# Power_Sheet.net
KiCad netlist of a schematic drawn in Altium Designer
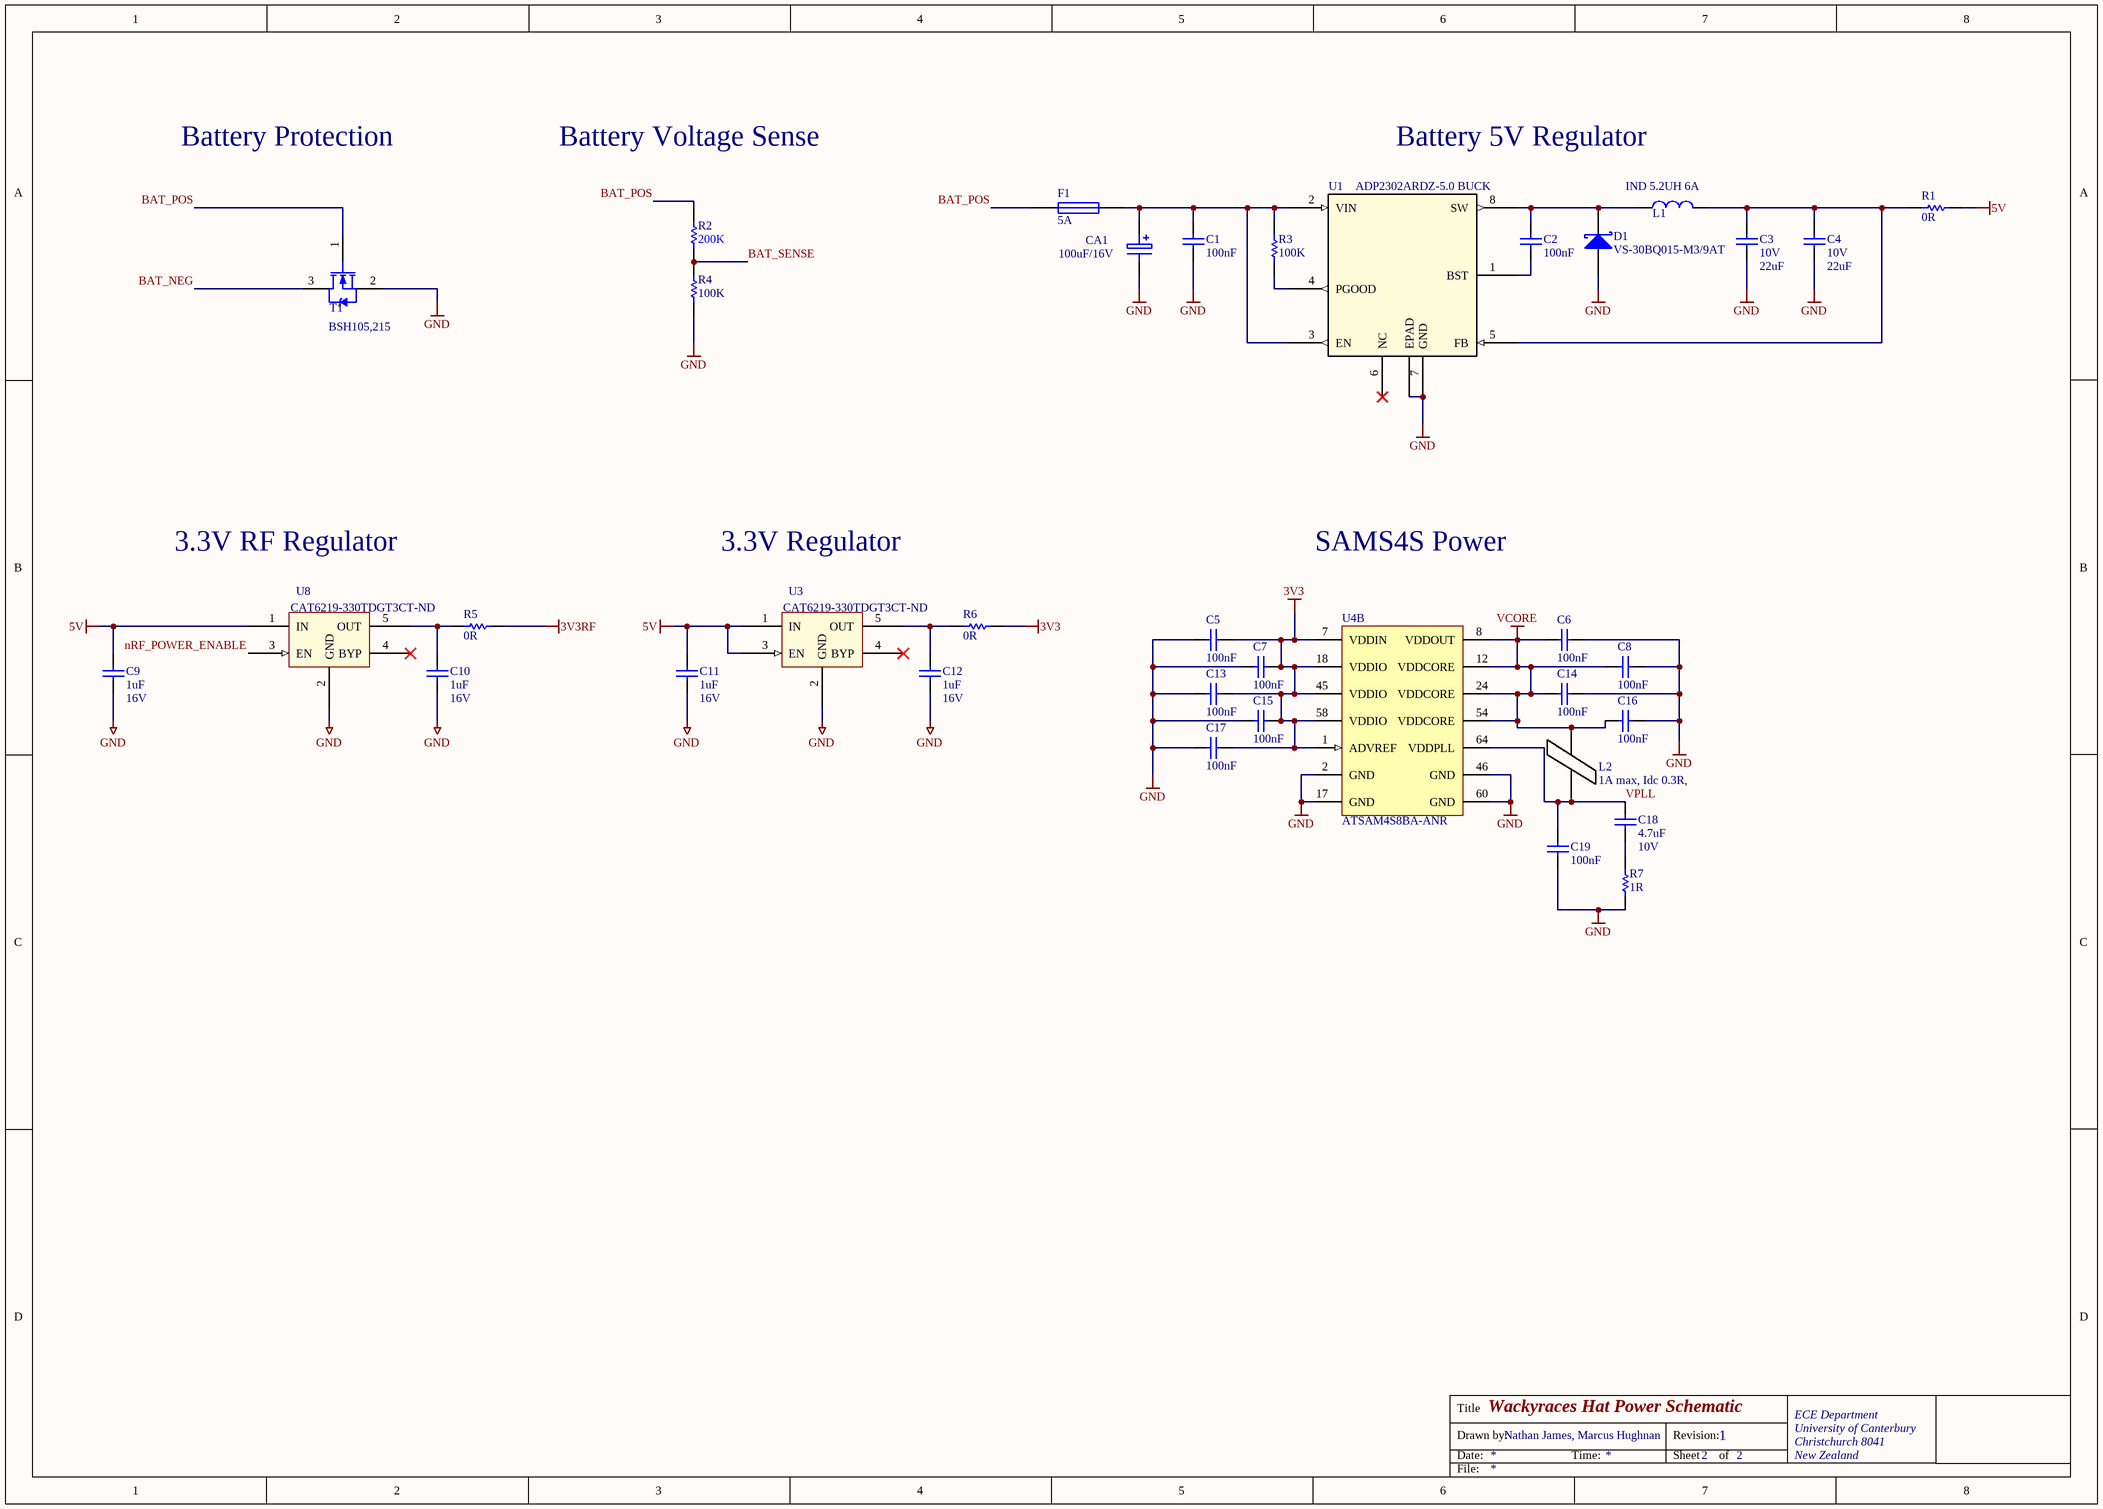
[diagram p0: Power Sheet.SchDoc]

(export (version "E")
  (design (tool "Eeschema 10.0.6"))
  (components
    (comp (ref "C1")
      (value "100nF")
      (footprint "CAPC1608L")
      (description "CAP CER 100nF X7R +-10% 50V 0603")
      (libsource (lib "ECE AD19Components_19V1") (part "CC_100nF_0603"))
    )
    (comp (ref "C2")
      (value "100nF")
      (footprint "CAPC1608L")
      (description "CAP CER 100nF X7R +-10% 50V 0603")
      (libsource (lib "ECE AD19Components_19V1") (part "CC_100nF_0603"))
    )
    (comp (ref "C3")
      (value "22uF")
      (footprint "CAPC3216L")
      (description "CAP CER 22uF Y5V -20% +80% 10V 1206")
      (fields (field (name "MAX VOLTAGE") "10V"))
      (libsource (lib "ECE AD19Components_19V1") (part "CC_22uF_1206"))
    )
    (comp (ref "C4")
      (value "22uF")
      (footprint "CAPC3216L")
      (description "CAP CER 22uF Y5V -20% +80% 10V 1206")
      (fields (field (name "MAX VOLTAGE") "10V"))
      (libsource (lib "ECE AD19Components_19V1") (part "CC_22uF_1206"))
    )
    (comp (ref "C5")
      (value "100nF")
      (footprint "CAPC1608L")
      (description "CAP CER 100nF X7R +-10% 50V 0603")
      (libsource (lib "ECE AD19Components_19V1") (part "CC_100nF_0603"))
    )
    (comp (ref "C6")
      (value "100nF")
      (footprint "CAPC1608L")
      (description "CAP CER 100nF X7R +-10% 50V 0603")
      (libsource (lib "ECE AD19Components_19V1") (part "CC_100nF_0603"))
    )
    (comp (ref "C7")
      (value "100nF")
      (footprint "CAPC1608L")
      (description "CAP CER 100nF X7R +-10% 50V 0603")
      (libsource (lib "ECE AD19Components_19V1") (part "CC_100nF_0603"))
    )
    (comp (ref "C8")
      (value "100nF")
      (footprint "CAPC1608L")
      (description "CAP CER 100nF X7R +-10% 50V 0603")
      (libsource (lib "ECE AD19Components_19V1") (part "CC_100nF_0603"))
    )
    (comp (ref "C9")
      (value "1uF")
      (footprint "CAPC1608L")
      (description "CAP CER 1uF Y5V -20% +80% 16V 0603")
      (fields (field (name "MAX VOLTAGE") "16V"))
      (libsource (lib "ECE AD19Components_19V1") (part "CC_1uF_0603"))
    )
    (comp (ref "C10")
      (value "1uF")
      (footprint "CAPC1608L")
      (description "CAP CER 1uF Y5V -20% +80% 16V 0603")
      (fields (field (name "MAX VOLTAGE") "16V"))
      (libsource (lib "ECE AD19Components_19V1") (part "CC_1uF_0603"))
    )
    (comp (ref "C11")
      (value "1uF")
      (footprint "CAPC1608L")
      (description "CAP CER 1uF Y5V -20% +80% 16V 0603")
      (fields (field (name "MAX VOLTAGE") "16V"))
      (libsource (lib "ECE AD19Components_19V1") (part "CC_1uF_0603"))
    )
    (comp (ref "C12")
      (value "1uF")
      (footprint "CAPC1608L")
      (description "CAP CER 1uF Y5V -20% +80% 16V 0603")
      (fields (field (name "MAX VOLTAGE") "16V"))
      (libsource (lib "ECE AD19Components_19V1") (part "CC_1uF_0603"))
    )
    (comp (ref "C13")
      (value "100nF")
      (footprint "CAPC1608L")
      (description "CAP CER 100nF X7R +-10% 50V 0603")
      (libsource (lib "ECE AD19Components_19V1") (part "CC_100nF_0603"))
    )
    (comp (ref "C14")
      (value "100nF")
      (footprint "CAPC1608L")
      (description "CAP CER 100nF X7R +-10% 50V 0603")
      (libsource (lib "ECE AD19Components_19V1") (part "CC_100nF_0603"))
    )
    (comp (ref "C15")
      (value "100nF")
      (footprint "CAPC1608L")
      (description "CAP CER 100nF X7R +-10% 50V 0603")
      (libsource (lib "ECE AD19Components_19V1") (part "CC_100nF_0603"))
    )
    (comp (ref "C16")
      (value "100nF")
      (footprint "CAPC1608L")
      (description "CAP CER 100nF X7R +-10% 50V 0603")
      (libsource (lib "ECE AD19Components_19V1") (part "CC_100nF_0603"))
    )
    (comp (ref "C17")
      (value "100nF")
      (footprint "CAPC1608L")
      (description "CAP CER 100nF X7R +-10% 50V 0603")
      (libsource (lib "ECE AD19Components_19V1") (part "CC_100nF_0603"))
    )
    (comp (ref "C18")
      (value "4.7uF")
      (footprint "CAPC1608N")
      (description "CAP CER 4.7uF X5R +-20%  10V 0603")
      (fields (field (name "MAX VOLTAGE") "10V"))
      (libsource (lib "ECE AD19Components_19V1") (part "CC_4.7uF_0603"))
    )
    (comp (ref "C19")
      (value "100nF")
      (footprint "CAPC1608L")
      (description "CAP CER 100nF X7R +-10% 50V 0603")
      (libsource (lib "ECE AD19Components_19V1") (part "CC_100nF_0603"))
    )
    (comp (ref "CA1")
      (value "100uF/16V")
      (footprint "NICH-1")
      (description "CAP ALUM 100uF 16V SMD")
      (fields (field (name "MANUFACTURER") "Nichcon"))
      (libsource (lib "ECE AD19Components_19V1") (part "CA_100uF_16V"))
    )
    (comp (ref "D1")
      (value "VS-30BQ015-M3/9AT")
      (footprint "SMC")
      (description "DIODE, SCHOTTKY, 3A, 15V, DO-214AB / SMC")
      (fields (field (name "MANUFACTURER") "Vishay Semiconductors"))
      (libsource (lib "ECE AD19Components_19V1") (part "DS_VS-30BQ015-M3"))
    )
    (comp (ref "F1")
      (value "5A")
      (footprint "RESC3216N")
      (description "Fuse 5.0A Fast Acting 1206 SMD")
      (fields (field (name "MANUFACTURER PART NUMBER") "C1F5") (field (name "MANUFACTURER") "Bel TRP"))
      (libsource (lib "ECE AD19Components_19V1") (part "FS_Fuse_5.0A"))
    )
    (comp (ref "L1")
      (value "IND 5.2UH 6A")
      (footprint "INDUCTOR5u2")
      (description "FIXED IND 5.2UH 6A 22 MOHM SMD")
      (fields
        (field (name "MANUFACTURER") "Sumida America Components Inc.")
        (field (name "MANUFACTURER PART NUMBER") "CDRH104RNP-5R2NC")
      )
      (libsource (lib "ENCE461AD19_19V2") (part "CDRH104RNP-5R2NC"))
    )
    (comp (ref "L2")
      (value "1A max, Idc 0.3R,")
      (footprint "INDC3216L")
      (description "Ferrite Bead, Rdc 0.3R, Z100MHZ 600R, Imax 1A, SMD 1206")
      (fields
        (field (name "MANUFACTURER") "FAIR-RITE")
        (field (name "MANUFACTURER PART NUMBER") "2512066017Y1")
      )
      (libsource (lib "ECE AD19Components_19V1") (part "IN_Ferrite-Bead"))
    )
    (comp (ref "R1")
      (value "0R")
      (footprint "RESC1608L")
      (description "RES 0.0 OHM 1/10W 5% 0603 SMD")
      (libsource (lib "ECE AD19Components_19V1") (part "RS_0R0"))
    )
    (comp (ref "R2")
      (value "200K")
      (footprint "RESC1608L")
      (description "RES 200K OHM 1/10W 5% 0603 SMD")
      (libsource (lib "ECE AD19Components_19V1") (part "RS_200K"))
    )
    (comp (ref "R3")
      (value "100K")
      (footprint "RESC1608L")
      (description "RES 100K OHM 1/10W 5% 0603 SMD")
      (libsource (lib "ECE AD19Components_19V1") (part "RS_100K"))
    )
    (comp (ref "R4")
      (value "100K")
      (footprint "RESC1608L")
      (description "RES 100K OHM 1/10W 5% 0603 SMD")
      (libsource (lib "ECE AD19Components_19V1") (part "RS_100K"))
    )
    (comp (ref "R5")
      (value "0R")
      (footprint "RESC1608L")
      (description "RES 0.0 OHM 1/10W 5% 0603 SMD")
      (libsource (lib "ECE AD19Components_19V1") (part "RS_0R0"))
    )
    (comp (ref "R6")
      (value "0R")
      (footprint "RESC1608L")
      (description "RES 0.0 OHM 1/10W 5% 0603 SMD")
      (libsource (lib "ECE AD19Components_19V1") (part "RS_0R0"))
    )
    (comp (ref "R7")
      (value "1R")
      (footprint "RESC3216L")
      (description "RES 1R OHM 1/4W 5% 1206 SMD")
      (libsource (lib "ECE AD19Components_19V1") (part "RT_1R"))
    )
    (comp (ref "T1")
      (value "BSH105,215")
      (footprint "SOT23_L")
      (description "MOSFET N-CH 20V 1.05A SOT-23")
      (fields
        (field (name "MANUFACTURER") "NXP Semiconductors")
        (field (name "MANUFACTURER PART NUMBER") "BSH105,215")
      )
      (libsource (lib "ECE AD19Components_19V1") (part "TM_BSH105"))
    )
    (comp (ref "U1")
      (value "ADP2302ARDZ-5.0 BUCK")
      (footprint "RD_8_1")
      (description "IC REG BUCK 5V 2A 8SOIC")
      (fields (field (name "MANUFACTURER_PART_NUMBER") "ADP2302ARDZ-5.0-R7"))
      (libsource (lib "ENCE461AD19_19V2") (part "ADP2302ARDZ-5.0-R7"))
    )
    (comp (ref "U3")
      (value "CAT6219-330TDGT3")
      (footprint "SOT95P280X145-5N")
      (description "IC REG LIN 3.3V 500MA TSOT23-5")
      (fields
        (field (name "BASE PART NUMBER") "CAT6219")
        (field (name "SUPPLIER PART NUMBER") "CAT6219-330TDGT3CT-ND")
      )
      (libsource (lib "ENCE461AD19_19V2") (part "SV_CAT6219-330TDGT3"))
    )
    (comp (ref "U4")
      (value "ATSAM4S8BA-ANR")
      (footprint "LQFP64_L")
      (description "IC MCU 32BIT 512KB FLASH 64LQFP")
      (fields (field (name "MANUFACTURER") "Atmel"))
      (libsource (lib "ECE AD19Components_19V1") (part "SE_ATSAM4S16BA-MU"))
    )
    (comp (ref "U8")
      (value "CAT6219-330TDGT3")
      (footprint "SOT95P280X145-5N")
      (description "IC REG LIN 3.3V 500MA TSOT23-5")
      (fields
        (field (name "BASE PART NUMBER") "CAT6219")
        (field (name "SUPPLIER PART NUMBER") "CAT6219-330TDGT3CT-ND")
      )
      (libsource (lib "ENCE461AD19_19V2") (part "SV_CAT6219-330TDGT3"))
    )
  )
  (nets
    (net (code "1") (name "/BAT_NEG") (class "Default")
      (node (ref "T1") (pin "3") (pinfunction "3_3") (pintype "passive"))
    )
    (net (code "2") (name "/BAT_POS") (class "Default")
      (node (ref "F1") (pin "1") (pinfunction "1_1") (pintype "passive"))
      (node (ref "R2") (pin "2") (pinfunction "2_2") (pintype "passive"))
      (node (ref "T1") (pin "1") (pinfunction "1_1") (pintype "passive"))
    )
    (net (code "3") (name "/BAT_SENSE") (class "Default")
      (node (ref "R2") (pin "1") (pinfunction "1_1") (pintype "passive"))
      (node (ref "R4") (pin "2") (pinfunction "2_2") (pintype "passive"))
    )
    (net (code "4") (name "/VPLL") (class "Default")
      (node (ref "C18") (pin "2") (pinfunction "2_2") (pintype "passive"))
      (node (ref "C19") (pin "2") (pinfunction "2_2") (pintype "passive"))
      (node (ref "L2") (pin "1") (pinfunction "1_1") (pintype "passive"))
      (node (ref "U4") (pin "64") (pinfunction "VDDPLL_64") (pintype "power_in"))
    )
    (net (code "5") (name "/nRF_POWER_ENABLE") (class "Default")
      (node (ref "U8") (pin "3") (pinfunction "EN_3") (pintype "input"))
    )
    (net (code "6") (name "3V3") (class "Default")
      (node (ref "C13") (pin "2") (pinfunction "2_2") (pintype "passive"))
      (node (ref "C15") (pin "2") (pinfunction "2_2") (pintype "passive"))
      (node (ref "C17") (pin "2") (pinfunction "2_2") (pintype "passive"))
      (node (ref "C5") (pin "2") (pinfunction "2_2") (pintype "passive"))
      (node (ref "C7") (pin "2") (pinfunction "2_2") (pintype "passive"))
      (node (ref "R6") (pin "2") (pinfunction "2_2") (pintype "passive"))
      (node (ref "U4") (pin "1") (pinfunction "ADVREF_1") (pintype "input"))
      (node (ref "U4") (pin "18") (pinfunction "VDDIO_18") (pintype "power_in"))
      (node (ref "U4") (pin "45") (pinfunction "VDDIO_45") (pintype "power_in"))
      (node (ref "U4") (pin "58") (pinfunction "VDDIO_58") (pintype "power_in"))
      (node (ref "U4") (pin "7") (pinfunction "VDDIN_7") (pintype "power_in"))
    )
    (net (code "7") (name "3V3RF") (class "Default")
      (node (ref "R5") (pin "2") (pinfunction "2_2") (pintype "passive"))
    )
    (net (code "8") (name "5V") (class "Default")
      (node (ref "C11") (pin "2") (pinfunction "2_2") (pintype "passive"))
      (node (ref "C9") (pin "2") (pinfunction "2_2") (pintype "passive"))
      (node (ref "R1") (pin "2") (pinfunction "2_2") (pintype "passive"))
      (node (ref "U3") (pin "1") (pinfunction "IN_1") (pintype "power_in"))
      (node (ref "U3") (pin "3") (pinfunction "EN_3") (pintype "input"))
      (node (ref "U8") (pin "1") (pinfunction "IN_1") (pintype "power_in"))
    )
    (net (code "9") (name "GND") (class "Default")
      (node (ref "C1") (pin "1") (pinfunction "1_1") (pintype "passive"))
      (node (ref "C10") (pin "1") (pinfunction "1_1") (pintype "passive"))
      (node (ref "C11") (pin "1") (pinfunction "1_1") (pintype "passive"))
      (node (ref "C12") (pin "1") (pinfunction "1_1") (pintype "passive"))
      (node (ref "C13") (pin "1") (pinfunction "1_1") (pintype "passive"))
      (node (ref "C14") (pin "2") (pinfunction "2_2") (pintype "passive"))
      (node (ref "C15") (pin "1") (pinfunction "1_1") (pintype "passive"))
      (node (ref "C16") (pin "2") (pinfunction "2_2") (pintype "passive"))
      (node (ref "C17") (pin "1") (pinfunction "1_1") (pintype "passive"))
      (node (ref "C19") (pin "1") (pinfunction "1_1") (pintype "passive"))
      (node (ref "C3") (pin "1") (pinfunction "1_1") (pintype "passive"))
      (node (ref "C4") (pin "1") (pinfunction "1_1") (pintype "passive"))
      (node (ref "C5") (pin "1") (pinfunction "1_1") (pintype "passive"))
      (node (ref "C6") (pin "2") (pinfunction "2_2") (pintype "passive"))
      (node (ref "C7") (pin "1") (pinfunction "1_1") (pintype "passive"))
      (node (ref "C8") (pin "2") (pinfunction "2_2") (pintype "passive"))
      (node (ref "C9") (pin "1") (pinfunction "1_1") (pintype "passive"))
      (node (ref "CA1") (pin "1") (pintype "passive"))
      (node (ref "D1") (pin "1") (pinfunction "A_1") (pintype "passive"))
      (node (ref "R4") (pin "1") (pinfunction "1_1") (pintype "passive"))
      (node (ref "R7") (pin "1") (pinfunction "1_1") (pintype "passive"))
      (node (ref "T1") (pin "2") (pinfunction "2_2") (pintype "passive"))
      (node (ref "U1") (pin "7") (pinfunction "GND_7") (pintype "power_in"))
      (node (ref "U1") (pin "EPAD") (pinfunction "EPAD_EPAD") (pintype "passive"))
      (node (ref "U3") (pin "2") (pinfunction "GND_2") (pintype "power_in"))
      (node (ref "U4") (pin "17") (pinfunction "GND_17") (pintype "power_in"))
      (node (ref "U4") (pin "2") (pinfunction "GND_2") (pintype "power_in"))
      (node (ref "U4") (pin "46") (pinfunction "GND_46") (pintype "power_in"))
      (node (ref "U4") (pin "60") (pinfunction "GND_60") (pintype "power_in"))
      (node (ref "U8") (pin "2") (pinfunction "GND_2") (pintype "power_in"))
    )
    (net (code "10") (name "Net-(C18-Pad1)") (class "Default")
      (node (ref "C18") (pin "1") (pinfunction "1_1") (pintype "passive"))
      (node (ref "R7") (pin "2") (pinfunction "2_2") (pintype "passive"))
    )
    (net (code "11") (name "Net-(D1-K)") (class "Default")
      (node (ref "C2") (pin "2") (pinfunction "2_2") (pintype "passive"))
      (node (ref "D1") (pin "2") (pinfunction "K_2") (pintype "passive"))
      (node (ref "L1") (pin "1") (pintype "passive"))
      (node (ref "U1") (pin "8") (pinfunction "SW_8") (pintype "output"))
    )
    (net (code "12") (name "Net-(U1-BST)") (class "Default")
      (node (ref "C2") (pin "1") (pinfunction "1_1") (pintype "passive"))
      (node (ref "U1") (pin "1") (pinfunction "BST_1") (pintype "passive"))
    )
    (net (code "13") (name "Net-(U1-EN)") (class "Default")
      (node (ref "C1") (pin "2") (pinfunction "2_2") (pintype "passive"))
      (node (ref "CA1") (pin "2") (pintype "passive"))
      (node (ref "F1") (pin "2") (pinfunction "2_2") (pintype "passive"))
      (node (ref "R3") (pin "1") (pinfunction "1_1") (pintype "passive"))
      (node (ref "U1") (pin "2") (pinfunction "VIN_2") (pintype "input"))
      (node (ref "U1") (pin "3") (pinfunction "EN_3") (pintype "output"))
    )
    (net (code "14") (name "Net-(U1-FB)") (class "Default")
      (node (ref "C3") (pin "2") (pinfunction "2_2") (pintype "passive"))
      (node (ref "C4") (pin "2") (pinfunction "2_2") (pintype "passive"))
      (node (ref "L1") (pin "2") (pintype "passive"))
      (node (ref "R1") (pin "1") (pinfunction "1_1") (pintype "passive"))
      (node (ref "U1") (pin "5") (pinfunction "FB_5") (pintype "input"))
    )
    (net (code "15") (name "Net-(U1-PGOOD)") (class "Default")
      (node (ref "R3") (pin "2") (pinfunction "2_2") (pintype "passive"))
      (node (ref "U1") (pin "4") (pinfunction "PGOOD_4") (pintype "output"))
    )
    (net (code "16") (name "Net-(U3-OUT)") (class "Default")
      (node (ref "C12") (pin "2") (pinfunction "2_2") (pintype "passive"))
      (node (ref "R6") (pin "1") (pinfunction "1_1") (pintype "passive"))
      (node (ref "U3") (pin "5") (pinfunction "OUT_5") (pintype "power_in"))
    )
    (net (code "17") (name "Net-(U8-OUT)") (class "Default")
      (node (ref "C10") (pin "2") (pinfunction "2_2") (pintype "passive"))
      (node (ref "R5") (pin "1") (pinfunction "1_1") (pintype "passive"))
      (node (ref "U8") (pin "5") (pinfunction "OUT_5") (pintype "power_in"))
    )
    (net (code "18") (name "VCORE") (class "Default")
      (node (ref "C14") (pin "1") (pinfunction "1_1") (pintype "passive"))
      (node (ref "C16") (pin "1") (pinfunction "1_1") (pintype "passive"))
      (node (ref "C6") (pin "1") (pinfunction "1_1") (pintype "passive"))
      (node (ref "C8") (pin "1") (pinfunction "1_1") (pintype "passive"))
      (node (ref "L2") (pin "2") (pinfunction "2_2") (pintype "passive"))
      (node (ref "U4") (pin "12") (pinfunction "VDDCORE_12") (pintype "power_in"))
      (node (ref "U4") (pin "24") (pinfunction "VDDCORE_24") (pintype "power_in"))
      (node (ref "U4") (pin "54") (pinfunction "VDDCORE_54") (pintype "power_in"))
      (node (ref "U4") (pin "8") (pinfunction "VDDOUT_8") (pintype "power_in"))
    )
    (net (code "19") (name "unconnected-(U1-NC-Pad6)") (class "Default")
      (node (ref "U1") (pin "6") (pinfunction "NC_6") (pintype "passive+no_connect"))
    )
    (net (code "20") (name "unconnected-(U3-BYP-Pad4)") (class "Default")
      (node (ref "U3") (pin "4") (pinfunction "BYP_4") (pintype "passive+no_connect"))
    )
    (net (code "21") (name "unconnected-(U8-BYP-Pad4)") (class "Default")
      (node (ref "U8") (pin "4") (pinfunction "BYP_4") (pintype "passive+no_connect"))
    )
  )
)
